# WalkMod.net
KiCad netlist of a schematic drawn in Altium Designer
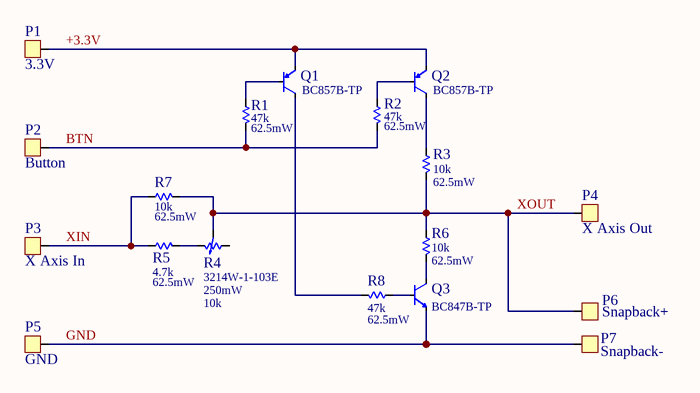
[diagram p0: WalkMod.SchDoc]

(export (version "E")
  (design (tool "Eeschema 10.0.6"))
  (components
    (comp (ref "P1")
      (value "SMD Pad 1 pin")
      (footprint "PAD_4X1.5")
      (description "Single SMD Pad")
      (fields (field (name "NAME") "3.3V"))
      (libsource (lib "WalkMod") (part "SMD Pad 1 pin"))
    )
    (comp (ref "P2")
      (value "SMD Pad 1 pin")
      (footprint "PAD_4X1.5")
      (description "Single SMD Pad")
      (fields (field (name "NAME") "Button"))
      (libsource (lib "WalkMod") (part "SMD Pad 1 pin"))
    )
    (comp (ref "P3")
      (value "SMD Pad 1 pin")
      (footprint "PAD_4X1.5")
      (description "Single SMD Pad")
      (fields (field (name "NAME") "X Axis In"))
      (libsource (lib "WalkMod") (part "SMD Pad 1 pin"))
    )
    (comp (ref "P4")
      (value "SMD Pad 1 pin")
      (footprint "PAD_4X1.5")
      (description "Single SMD Pad")
      (fields (field (name "NAME") "X Axis Out"))
      (libsource (lib "") (part "SMD Pad 1 pin_1"))
    )
    (comp (ref "P5")
      (value "SMD Pad 1 pin")
      (footprint "PAD_4X1.5")
      (description "Single SMD Pad")
      (fields (field (name "NAME") "GND"))
      (libsource (lib "WalkMod") (part "SMD Pad 1 pin"))
    )
    (comp (ref "P6")
      (value "SMD Pad 1 pin")
      (footprint "PAD_0.95X1.8")
      (description "Single SMD Pad")
      (fields (field (name "NAME") "Snapback+"))
      (libsource (lib "") (part "SMD Pad 1 pin_1"))
    )
    (comp (ref "P7")
      (value "SMD Pad 1 pin")
      (footprint "PAD_0.95X1.8")
      (description "Single SMD Pad")
      (fields (field (name "NAME") "Snapback-"))
      (libsource (lib "") (part "SMD Pad 1 pin_1"))
    )
    (comp (ref "Q1")
      (value "BC857B-TP")
      (footprint "BC8xx_SOT23-3_C")
      (description "Bipolar (BJT) Transistor PNP 45 V 100 mA 200MHz 310 mW Surface Mount SOT-23")
      (libsource (lib "WalkMod") (part "BC857B-TP"))
    )
    (comp (ref "Q2")
      (value "BC857B-TP")
      (footprint "BC8xx_SOT23-3_C")
      (description "Bipolar (BJT) Transistor PNP 45 V 100 mA 200MHz 310 mW Surface Mount SOT-23")
      (libsource (lib "WalkMod") (part "BC857B-TP"))
    )
    (comp (ref "Q3")
      (value "BC847B-TP")
      (footprint "BC8xx_SOT23-3_C")
      (description "Bipolar (BJT) Transistor NPN 45 V 100 mA 100MHz 225 mW Surface Mount SOT-23")
      (libsource (lib "WalkMod") (part "BC847B-TP"))
    )
    (comp (ref "R1")
      (value "47k")
      (footprint "RT0402")
      (description "47 kOhms ±0.5% 0.063W, 1/16W Chip Resistor 0402 (1005 Metric) - Thin Film")
      (fields (field (name "VALUE2") "62.5mW") (field (name "Comment") "RT0402DRD0747KL"))
      (libsource (lib "WalkMod") (part "RT0402DRD0747KL"))
    )
    (comp (ref "R2")
      (value "47k")
      (footprint "RT0402")
      (description "47 kOhms ±0.5% 0.063W, 1/16W Chip Resistor 0402 (1005 Metric) - Thin Film")
      (fields (field (name "VALUE2") "62.5mW") (field (name "Comment") "RT0402DRD0747KL"))
      (libsource (lib "WalkMod") (part "RT0402DRD0747KL"))
    )
    (comp (ref "R3")
      (value "10k")
      (footprint "AT0402")
      (fields (field (name "VALUE2") "62.5mW") (field (name "Comment") "AT0402FRE0710KL"))
      (libsource (lib "WalkMod") (part "AT0402FRE0710KL"))
    )
    (comp (ref "R4")
      (value "3214W-1-103E")
      (footprint "BOURNS_3214W_C")
      (description "10 kOhms 0.25W, 1/4W J Lead Surface Mount Trimmer Potentiometer Cermet 5.0 Turn Top Adjustment")
      (fields (field (name "VALUE2") "250mW") (field (name "ALTIUM_VALUE") "10k"))
      (libsource (lib "WalkMod") (part "3214W-1-103E"))
    )
    (comp (ref "R5")
      (value "4.7k")
      (footprint "RT0402")
      (description "4.7 kOhms ±1% 0.063W, 1/16W Chip Resistor 0402 (1005 Metric) - Thin Film")
      (fields (field (name "VALUE2") "62.5mW") (field (name "Comment") "RT0402FRE074K7L"))
      (libsource (lib "WalkMod") (part "RT0402FRE074K7L"))
    )
    (comp (ref "R6")
      (value "10k")
      (footprint "AT0402")
      (fields (field (name "VALUE2") "62.5mW") (field (name "Comment") "AT0402FRE0710KL"))
      (libsource (lib "WalkMod") (part "AT0402FRE0710KL"))
    )
    (comp (ref "R7")
      (value "10k")
      (footprint "AT0402")
      (fields (field (name "VALUE2") "62.5mW") (field (name "Comment") "AT0402FRE0710KL"))
      (libsource (lib "WalkMod") (part "AT0402FRE0710KL"))
    )
    (comp (ref "R8")
      (value "47k")
      (footprint "RT0402")
      (description "47 kOhms ±0.5% 0.063W, 1/16W Chip Resistor 0402 (1005 Metric) - Thin Film")
      (fields (field (name "VALUE2") "62.5mW") (field (name "Comment") "RT0402DRD0747KL"))
      (libsource (lib "WalkMod") (part "RT0402DRD0747KL"))
    )
  )
  (nets
    (net (code "1") (name "/+3.3V") (class "Default")
      (node (ref "P1") (pin "1") (pinfunction "1_1") (pintype "passive"))
      (node (ref "Q1") (pin "E") (pinfunction "E_E") (pintype "passive"))
      (node (ref "Q2") (pin "E") (pinfunction "E_E") (pintype "passive"))
    )
    (net (code "2") (name "/BTN") (class "Default")
      (node (ref "P2") (pin "1") (pinfunction "1_1") (pintype "passive"))
      (node (ref "R1") (pin "1") (pinfunction "1_1") (pintype "passive"))
      (node (ref "R2") (pin "1") (pinfunction "1_1") (pintype "passive"))
    )
    (net (code "3") (name "/GND") (class "Default")
      (node (ref "P5") (pin "1") (pinfunction "1_1") (pintype "passive"))
      (node (ref "P7") (pin "1") (pinfunction "1_1") (pintype "passive"))
      (node (ref "Q3") (pin "E") (pinfunction "E_E") (pintype "passive"))
    )
    (net (code "4") (name "/XIN") (class "Default")
      (node (ref "P3") (pin "1") (pinfunction "1_1") (pintype "passive"))
      (node (ref "R5") (pin "1") (pinfunction "1_1") (pintype "passive"))
      (node (ref "R7") (pin "2") (pinfunction "2_2") (pintype "passive"))
    )
    (net (code "5") (name "/XOUT") (class "Default")
      (node (ref "P4") (pin "1") (pinfunction "1_1") (pintype "passive"))
      (node (ref "P6") (pin "1") (pinfunction "1_1") (pintype "passive"))
      (node (ref "R3") (pin "2") (pinfunction "2_2") (pintype "passive"))
      (node (ref "R4") (pin "2") (pinfunction "2_2") (pintype "passive"))
      (node (ref "R6") (pin "1") (pinfunction "1_1") (pintype "passive"))
      (node (ref "R7") (pin "1") (pinfunction "1_1") (pintype "passive"))
    )
    (net (code "6") (name "Net-(Q1-PadB)") (class "Default")
      (node (ref "Q1") (pin "B") (pinfunction "B_B") (pintype "passive"))
      (node (ref "R1") (pin "2") (pinfunction "2_2") (pintype "passive"))
    )
    (net (code "7") (name "Net-(Q1-PadC)") (class "Default")
      (node (ref "Q1") (pin "C") (pinfunction "C_C") (pintype "passive"))
      (node (ref "R8") (pin "1") (pinfunction "1_1") (pintype "passive"))
    )
    (net (code "8") (name "Net-(Q2-PadB)") (class "Default")
      (node (ref "Q2") (pin "B") (pinfunction "B_B") (pintype "passive"))
      (node (ref "R2") (pin "2") (pinfunction "2_2") (pintype "passive"))
    )
    (net (code "9") (name "Net-(Q2-PadC)") (class "Default")
      (node (ref "Q2") (pin "C") (pinfunction "C_C") (pintype "passive"))
      (node (ref "R3") (pin "1") (pinfunction "1_1") (pintype "passive"))
    )
    (net (code "10") (name "Net-(Q3-PadB)") (class "Default")
      (node (ref "Q3") (pin "B") (pinfunction "B_B") (pintype "passive"))
      (node (ref "R8") (pin "2") (pinfunction "2_2") (pintype "passive"))
    )
    (net (code "11") (name "Net-(Q3-PadC)") (class "Default")
      (node (ref "Q3") (pin "C") (pinfunction "C_C") (pintype "passive"))
      (node (ref "R6") (pin "2") (pinfunction "2_2") (pintype "passive"))
    )
    (net (code "12") (name "Net-(R4-Pad3)") (class "Default")
      (node (ref "R4") (pin "3") (pinfunction "3_3") (pintype "passive"))
      (node (ref "R5") (pin "2") (pinfunction "2_2") (pintype "passive"))
    )
    (net (code "13") (name "unconnected-(R4-Pad1)") (class "Default")
      (node (ref "R4") (pin "1") (pinfunction "1_1") (pintype "passive"))
    )
  )
)
